# LINE_SENSOR.net
KiCad netlist of a schematic drawn in Altium Designer
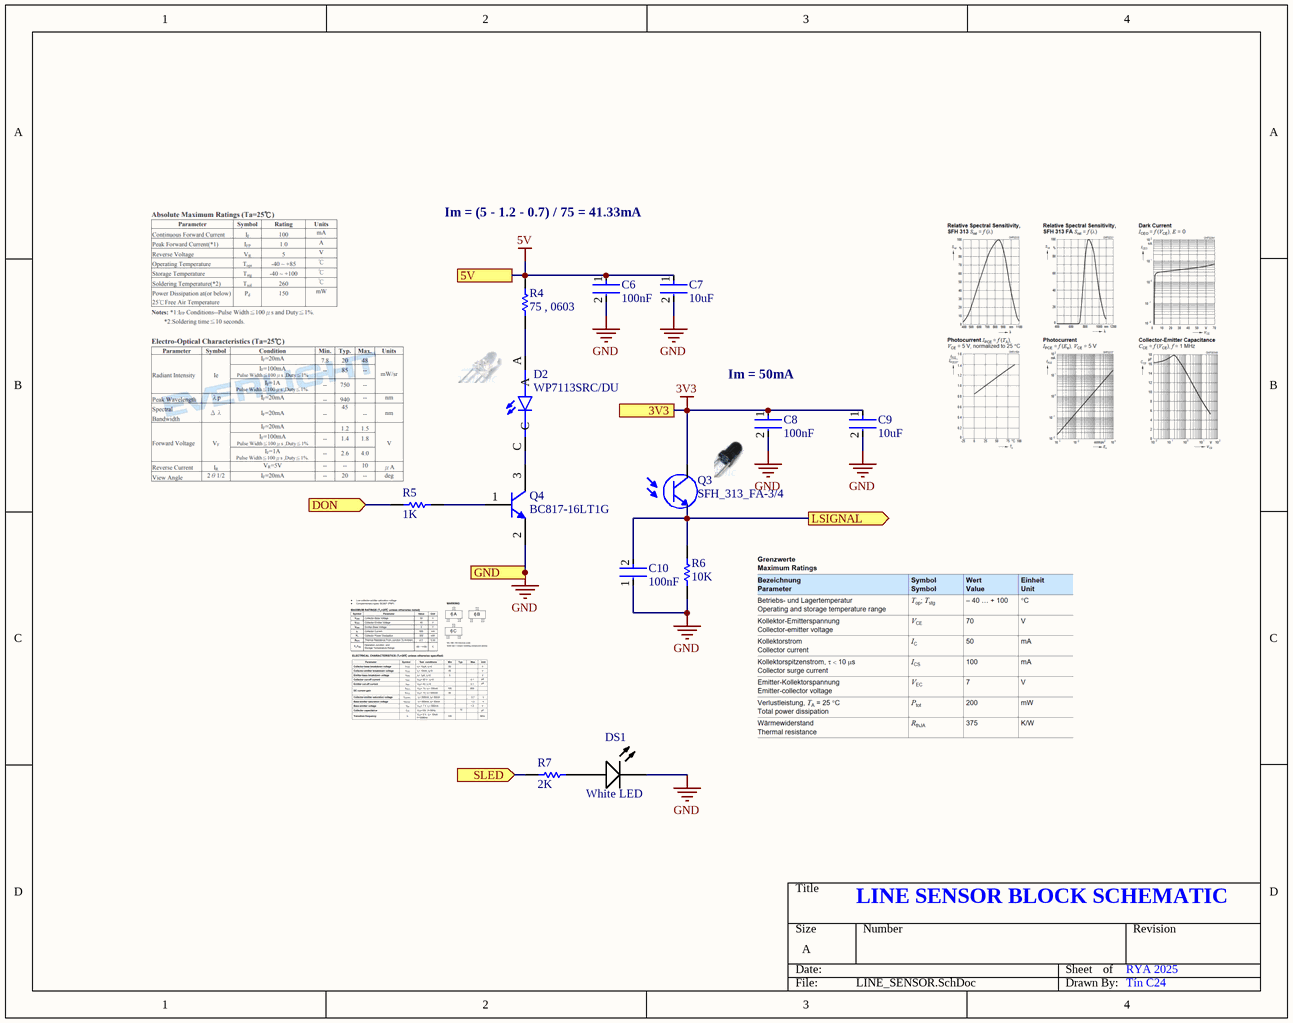
[diagram p0: LINE_SENSOR.SchDoc]

(export (version "E")
  (design (tool "Eeschema 10.0.6"))
  (components
    (comp (ref "C6")
      (value "100nF")
      (footprint "FP-C0603C-CF-MFG")
      (description "CAP CER 20PF 50V 5% NP0 0603")
      (fields
        (field (name "MANUFACTURER PART NUMBER") "C0603C200J5GACTU")
        (field (name "MANUFACTURER") "KEMET")
      )
      (libsource (lib "Altium Content Vault") (part "b4654b650e69147ec39a6b967a45e02"))
    )
    (comp (ref "C7")
      (value "10uF")
      (footprint "FP-C0603C-CF-MFG")
      (description "CAP CER 20PF 50V 5% NP0 0603")
      (fields
        (field (name "MANUFACTURER PART NUMBER") "C0603C200J5GACTU")
        (field (name "MANUFACTURER") "KEMET")
      )
      (libsource (lib "Altium Content Vault") (part "b4654b650e69147ec39a6b967a45e02"))
    )
    (comp (ref "C8")
      (value "100nF")
      (footprint "FP-C0603C-CF-MFG")
      (description "CAP CER 20PF 50V 5% NP0 0603")
      (fields
        (field (name "MANUFACTURER PART NUMBER") "C0603C200J5GACTU")
        (field (name "MANUFACTURER") "KEMET")
      )
      (libsource (lib "Altium Content Vault") (part "b4654b650e69147ec39a6b967a45e02"))
    )
    (comp (ref "C9")
      (value "10uF")
      (footprint "FP-C0603C-CF-MFG")
      (description "CAP CER 20PF 50V 5% NP0 0603")
      (fields
        (field (name "MANUFACTURER PART NUMBER") "C0603C200J5GACTU")
        (field (name "MANUFACTURER") "KEMET")
      )
      (libsource (lib "Altium Content Vault") (part "b4654b650e69147ec39a6b967a45e02"))
    )
    (comp (ref "C10")
      (value "100nF")
      (footprint "FP-GRM15-MFG")
      (description "CAP CER 0.1UF 16V X7R 0402")
      (fields (field (name "MANUFACTURER PART NUMBER") "GRM155R71C104KA88D") (field (name "TOLERANCE") "10%"))
      (libsource (lib "Altium Content Vault") (part "236180d848d6139a670b325ea6854c9"))
    )
    (comp (ref "D2")
      (value "WP7113SRC/DU")
      (footprint "IR_LED_NOTBENDED")
      (description "Red 640nm LED Indication - Discrete 1.85V Radial")
      (fields (field (name "MF") "Kingbright"))
      (libsource (lib "IR_LED") (part "WP7113SRC/DU"))
    )
    (comp (ref "DS1")
      (value "White LED")
      (footprint "AVAG-HSMW-C191_V")
      (description "LED Uni-Color White, 78 mW, 20 mA, -40 to 85 degC, 2-Pin SMD, RoHS, Tape and Reel")
      (fields (field (name "POWER") "78mW") (field (name "MANUFACTURER") "Avago"))
      (libsource (lib "Tin Tran") (part "LED-WHITE-AK-2"))
    )
    (comp (ref "Q3")
      (value "SFH_313_FA-3/4")
      (footprint "PHOTODIODE_NOTBENDED")
      (description "Phototransistors 870nm Top View Radial - 2 Leads")
      (fields (field (name "MF") "OSRAM Opto") (field (name "DIGI-KEY_PART_NUMBER") "475-3328-ND"))
      (libsource (lib "SFH_313_FA-3_4") (part "SFH_313_FA-3/4"))
    )
    (comp (ref "Q4")
      (value "BC817-16LT1G")
      (footprint "ONSC-SOT-23-3-318-08_V")
      (description "General Purpose Transistor, NPN Silicon, 3-Pin SOT-23, Pb-Free, Tape and Reel")
      (fields (field (name "MANUFACTURER") "On Semiconductor"))
      (libsource (lib "Altium Content Vault") (part "ONSC-NPN-B1E2C3-3"))
    )
    (comp (ref "R4")
      (value "75 , 0603")
      (footprint "RESC1608X55X25LL10T15")
      (fields (field (name "TOLERANCE") "1%") (field (name "MANUFACTURER") "Yageo"))
      (libsource (lib "Altium Content Vault") (part "RES-2"))
    )
    (comp (ref "R5")
      (value "1K")
      (footprint "RESC1005X40X25LL05T05")
      (description "0402 , 1KOhm")
      (fields (field (name "MANUFACTURER") "Panasonic") (field (name "TOLERANCE") "5%"))
      (libsource (lib "Altium Content Vault") (part "RES-2"))
    )
    (comp (ref "R6")
      (value "10K")
      (footprint "RESC1005X40X25LL05T05")
      (description "Chip Resistor, 0 Ohm, 0.1 W, -55 to 155 degC, 0402 (1005 Metric), RoHS, Tape and Reel")
      (fields (field (name "MANUFACTURER") "Panasonic") (field (name "TOLERANCE") "5%"))
      (libsource (lib "Altium Content Vault") (part "RES-2"))
    )
    (comp (ref "R7")
      (value "2K")
      (footprint "RESC1005X40X25LL05T05")
      (description "Chip Resistor, 0 Ohm, 0.1 W, -55 to 155 degC, 0402 (1005 Metric), RoHS, Tape and Reel")
      (fields (field (name "MANUFACTURER") "Panasonic") (field (name "TOLERANCE") "5%"))
      (libsource (lib "Altium Content Vault") (part "RES-2"))
    )
  )
  (nets
    (net (code "1") (name "/DON") (class "Default")
      (node (ref "R5") (pin "2") (pinfunction "2_2") (pintype "passive"))
    )
    (net (code "2") (name "/LSIGNAL") (class "Default")
      (node (ref "C10") (pin "2") (pinfunction "2_2") (pintype "passive"))
      (node (ref "Q3") (pin "1") (pinfunction "E_1") (pintype "passive"))
      (node (ref "R6") (pin "1") (pinfunction "1_1") (pintype "passive"))
    )
    (net (code "3") (name "/SLED") (class "Default")
      (node (ref "R7") (pin "1") (pinfunction "1_1") (pintype "passive"))
    )
    (net (code "4") (name "3V3") (class "Default")
      (node (ref "C8") (pin "1") (pinfunction "1_1") (pintype "passive"))
      (node (ref "C9") (pin "1") (pinfunction "1_1") (pintype "passive"))
      (node (ref "Q3") (pin "2") (pinfunction "C_2") (pintype "passive"))
    )
    (net (code "5") (name "5V") (class "Default")
      (node (ref "C6") (pin "1") (pinfunction "1_1") (pintype "passive"))
      (node (ref "C7") (pin "1") (pinfunction "1_1") (pintype "passive"))
      (node (ref "R4") (pin "2") (pinfunction "2_2") (pintype "passive"))
    )
    (net (code "6") (name "GND") (class "Default")
      (node (ref "C10") (pin "1") (pinfunction "1_1") (pintype "passive"))
      (node (ref "C6") (pin "2") (pinfunction "2_2") (pintype "passive"))
      (node (ref "C7") (pin "2") (pinfunction "2_2") (pintype "passive"))
      (node (ref "C8") (pin "2") (pinfunction "2_2") (pintype "passive"))
      (node (ref "C9") (pin "2") (pinfunction "2_2") (pintype "passive"))
      (node (ref "DS1") (pin "2") (pinfunction "K_2") (pintype "passive"))
      (node (ref "Q4") (pin "2") (pinfunction "E_2") (pintype "passive"))
      (node (ref "R6") (pin "2") (pinfunction "2_2") (pintype "passive"))
    )
    (net (code "7") (name "Net-(D2-PadA)") (class "Default")
      (node (ref "D2") (pin "A") (pinfunction "A_A") (pintype "passive"))
      (node (ref "R4") (pin "1") (pinfunction "1_1") (pintype "passive"))
    )
    (net (code "8") (name "Net-(DS1-A)") (class "Default")
      (node (ref "DS1") (pin "1") (pinfunction "A_1") (pintype "passive"))
      (node (ref "R7") (pin "2") (pinfunction "2_2") (pintype "passive"))
    )
    (net (code "9") (name "Net-(Q4-B)") (class "Default")
      (node (ref "Q4") (pin "1") (pinfunction "B_1") (pintype "passive"))
      (node (ref "R5") (pin "1") (pinfunction "1_1") (pintype "passive"))
    )
    (net (code "10") (name "Net-(Q4-C)") (class "Default")
      (node (ref "D2") (pin "C") (pinfunction "C_C") (pintype "passive"))
      (node (ref "Q4") (pin "3") (pinfunction "C_3") (pintype "passive"))
    )
  )
)
